# 5V_2576.net
KiCad netlist of a schematic drawn in Altium Designer
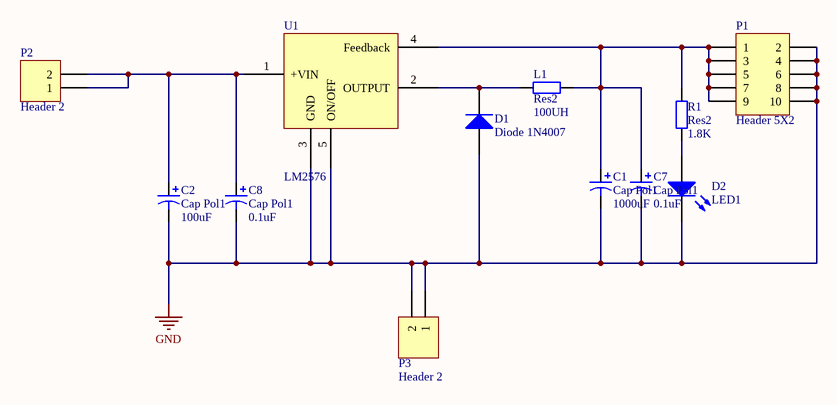
[diagram p0: +5V 2576.SchDoc]

(export (version "E")
  (design (tool "Eeschema 10.0.6"))
  (components
    (comp (ref "C1")
      (value "Cap Pol1")
      (footprint "CAPR5-4X5")
      (description "Polarized Capacitor (Radial)")
      (fields (field (name "ALTIUM_VALUE") "1000uF") (field (name "PUBLISHER") "Altium Limited"))
      (libsource (lib "Miscellaneous Devices") (part "Cap Pol1"))
    )
    (comp (ref "C2")
      (value "Cap Pol1")
      (footprint "CAPR5-4X5")
      (description "Polarized Capacitor (Radial)")
      (fields (field (name "ALTIUM_VALUE") "100uF") (field (name "PUBLISHER") "Altium Limited"))
      (libsource (lib "Miscellaneous Devices") (part "Cap Pol1"))
    )
    (comp (ref "C7")
      (value "Cap Pol1")
      (footprint "CAPR5-4X5")
      (description "Polarized Capacitor (Radial)")
      (fields (field (name "ALTIUM_VALUE") "0.1uF") (field (name "PUBLISHER") "Altium Limited"))
      (libsource (lib "Miscellaneous Devices") (part "Cap Pol1"))
    )
    (comp (ref "C8")
      (value "Cap Pol1")
      (footprint "CAPR5-4X5")
      (description "Polarized Capacitor (Radial)")
      (fields (field (name "ALTIUM_VALUE") "0.1uF") (field (name "PUBLISHER") "Altium Limited"))
      (libsource (lib "Miscellaneous Devices") (part "Cap Pol1"))
    )
    (comp (ref "D1")
      (value "Diode 1N4007")
      (footprint "SMB")
      (description "1 Amp General Purpose Rectifier")
      (fields (field (name "PUBLISHER") "Altium Limited"))
      (libsource (lib "Miscellaneous Devices") (part "Diode 1N4007"))
    )
    (comp (ref "D2")
      (value "LED1")
      (footprint "LED-1")
      (description "Typical RED GaAs LED")
      (fields (field (name "PUBLISHER") "Altium Limited"))
      (libsource (lib "Miscellaneous Devices") (part "LED1"))
    )
    (comp (ref "L1")
      (value "Res2")
      (footprint "AXIAL-0.4")
      (description "Resistor")
      (fields (field (name "ALTIUM_VALUE") "100UH") (field (name "PUBLISHER") "Altium Limited"))
      (libsource (lib "") (part "Res2_1"))
    )
    (comp (ref "P1")
      (value "Header 5X2")
      (footprint "HDR2X5")
      (description "Header, 5-Pin, Dual row")
      (fields (field (name "PUBLISHER") "Altium Limited"))
      (libsource (lib "Miscellaneous Connectors") (part "Header 5X2"))
    )
    (comp (ref "P2")
      (value "Header 2")
      (footprint "HDR1X2")
      (description "Header, 2-Pin")
      (fields (field (name "PUBLISHER") "Altium Limited"))
      (libsource (lib "Miscellaneous Connectors") (part "Header 2"))
    )
    (comp (ref "P3")
      (value "Header 2")
      (footprint "HDR1X2")
      (description "Header, 2-Pin")
      (fields (field (name "PUBLISHER") "Altium Limited"))
      (libsource (lib "") (part "Header 2_1"))
    )
    (comp (ref "R1")
      (value "Res2")
      (footprint "AXIAL-0.4")
      (description "Resistor")
      (fields (field (name "ALTIUM_VALUE") "1.8K") (field (name "PUBLISHER") "Altium Limited"))
      (libsource (lib "Miscellaneous Devices") (part "Res2"))
    )
    (comp (ref "U1") (value "LM2576") (footprint "LM2576") (libsource (lib "LM2576") (part "LM2576")))
  )
  (nets
    (net (code "1") (name "GND") (class "Default")
      (node (ref "C1") (pin "2") (pinfunction "2_2") (pintype "passive"))
      (node (ref "C2") (pin "2") (pinfunction "2_2") (pintype "passive"))
      (node (ref "C7") (pin "2") (pinfunction "2_2") (pintype "passive"))
      (node (ref "C8") (pin "2") (pinfunction "2_2") (pintype "passive"))
      (node (ref "D1") (pin "1") (pinfunction "A_1") (pintype "passive"))
      (node (ref "D2") (pin "2") (pinfunction "K_2") (pintype "passive"))
      (node (ref "P1") (pin "10") (pinfunction "10_10") (pintype "passive"))
      (node (ref "P1") (pin "2") (pinfunction "2_2") (pintype "passive"))
      (node (ref "P1") (pin "4") (pinfunction "4_4") (pintype "passive"))
      (node (ref "P1") (pin "6") (pinfunction "6_6") (pintype "passive"))
      (node (ref "P1") (pin "8") (pinfunction "8_8") (pintype "passive"))
      (node (ref "P3") (pin "1") (pinfunction "1_1") (pintype "passive"))
      (node (ref "P3") (pin "2") (pinfunction "2_2") (pintype "passive"))
      (node (ref "U1") (pin "3") (pinfunction "GND_3") (pintype "passive"))
      (node (ref "U1") (pin "5") (pinfunction "ON/OFF_5") (pintype "passive"))
    )
    (net (code "2") (name "Net-(D1-K)") (class "Default")
      (node (ref "D1") (pin "2") (pinfunction "K_2") (pintype "passive"))
      (node (ref "L1") (pin "1") (pinfunction "1_1") (pintype "passive"))
      (node (ref "U1") (pin "2") (pinfunction "OUTPUT_2") (pintype "passive"))
    )
    (net (code "3") (name "Net-(D2-A)") (class "Default")
      (node (ref "D2") (pin "1") (pinfunction "A_1") (pintype "passive"))
      (node (ref "R1") (pin "1") (pinfunction "1_1") (pintype "passive"))
    )
    (net (code "4") (name "Net-(U1-+VIN)") (class "Default")
      (node (ref "C2") (pin "1") (pinfunction "1_1") (pintype "passive"))
      (node (ref "C8") (pin "1") (pinfunction "1_1") (pintype "passive"))
      (node (ref "P2") (pin "1") (pinfunction "1_1") (pintype "passive"))
      (node (ref "P2") (pin "2") (pinfunction "2_2") (pintype "passive"))
      (node (ref "U1") (pin "1") (pinfunction "+VIN_1") (pintype "passive"))
    )
    (net (code "5") (name "Net-(U1-Feedback)") (class "Default")
      (node (ref "C1") (pin "1") (pinfunction "1_1") (pintype "passive"))
      (node (ref "C7") (pin "1") (pinfunction "1_1") (pintype "passive"))
      (node (ref "L1") (pin "2") (pinfunction "2_2") (pintype "passive"))
      (node (ref "P1") (pin "1") (pinfunction "1_1") (pintype "passive"))
      (node (ref "P1") (pin "3") (pinfunction "3_3") (pintype "passive"))
      (node (ref "P1") (pin "5") (pinfunction "5_5") (pintype "passive"))
      (node (ref "P1") (pin "7") (pinfunction "7_7") (pintype "passive"))
      (node (ref "P1") (pin "9") (pinfunction "9_9") (pintype "passive"))
      (node (ref "R1") (pin "2") (pinfunction "2_2") (pintype "passive"))
      (node (ref "U1") (pin "4") (pinfunction "Feedback_4") (pintype "passive"))
    )
  )
)
